# 2020.net
KiCad netlist of a schematic drawn in Altium Designer
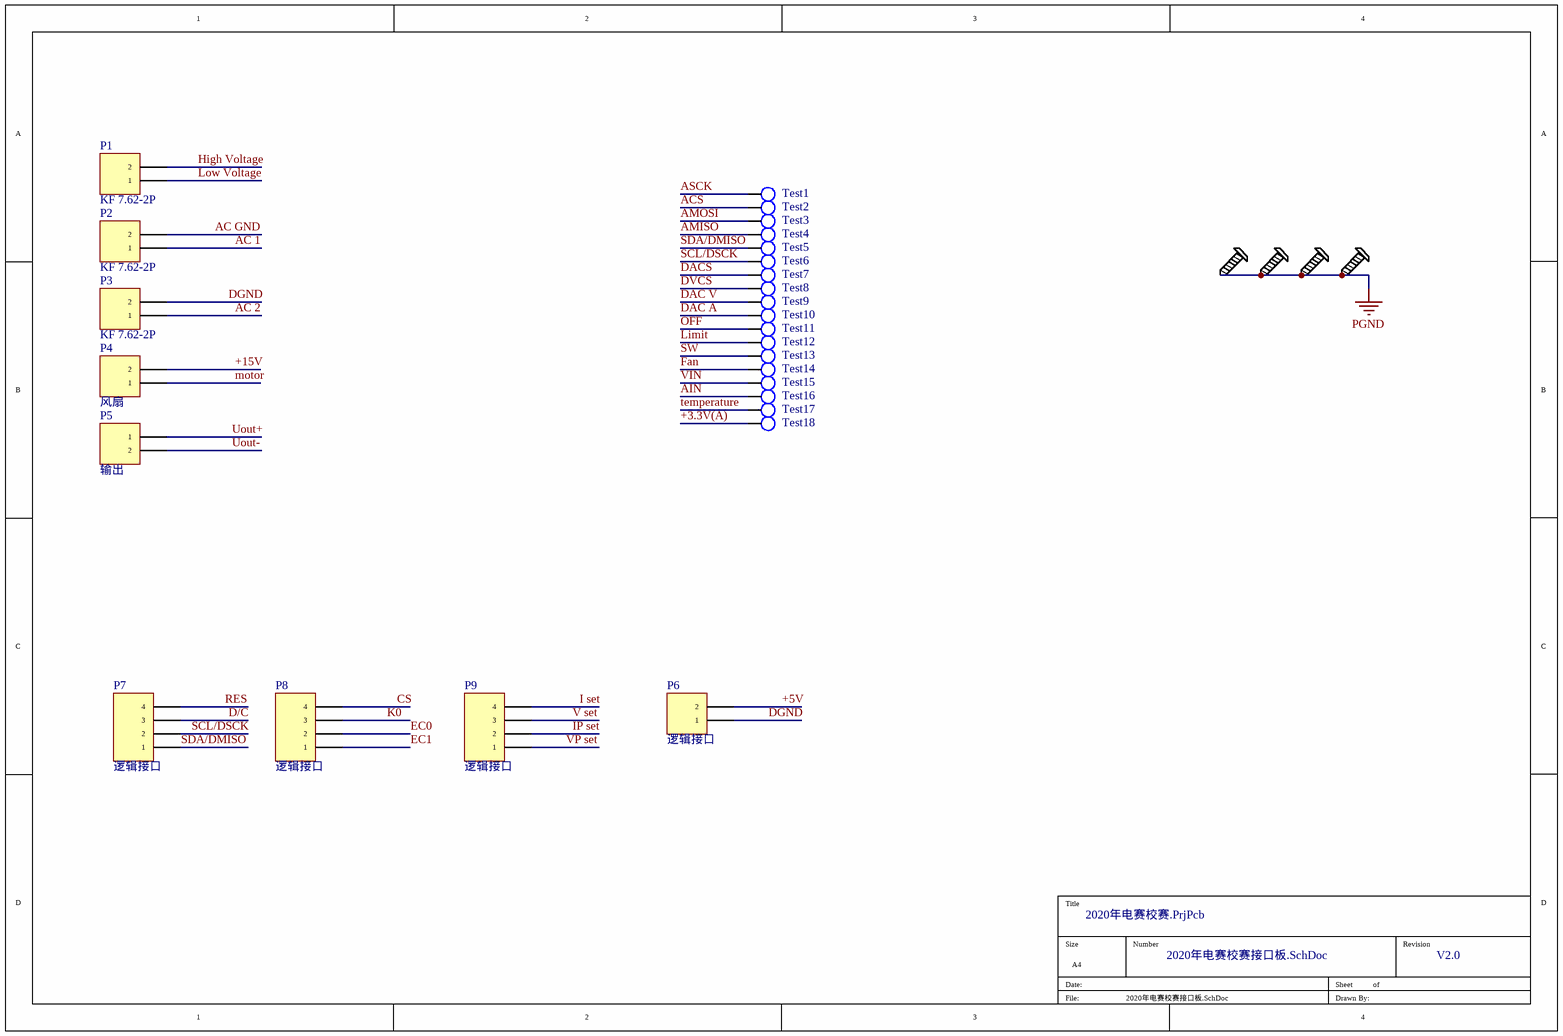
[diagram p0: 2020年电赛校赛接口板.SchDoc]

(export (version "E")
  (design (tool "Eeschema 10.0.6"))
  (components
    (comp (ref "P1")
      (value "KF 7.62-2P")
      (footprint "KF7.62-2P")
      (description "Header, 2-Pin")
      (fields (field (name "PUBLISHER") "Altium Limited"))
      (libsource (lib "Miscellaneous Connectors") (part "Header 2"))
    )
    (comp (ref "P2")
      (value "KF 7.62-2P")
      (footprint "KF7.62-2P")
      (description "Header, 2-Pin")
      (fields (field (name "PUBLISHER") "Altium Limited"))
      (libsource (lib "Miscellaneous Connectors") (part "Header 2"))
    )
    (comp (ref "P3")
      (value "KF 7.62-2P")
      (footprint "KF7.62-2P")
      (description "Header, 2-Pin")
      (fields (field (name "PUBLISHER") "Altium Limited"))
      (libsource (lib "Miscellaneous Connectors") (part "Header 2"))
    )
    (comp (ref "P4")
      (value "风扇")
      (footprint "XH2.54-2P")
      (description "Header, 2-Pin")
      (fields (field (name "PUBLISHER") "Altium Limited"))
      (libsource (lib "Miscellaneous Connectors") (part "Header 2"))
    )
    (comp (ref "P5")
      (value "输出")
      (footprint "KF7.62-2P")
      (description "Header, 2-Pin")
      (fields (field (name "PUBLISHER") "Altium Limited"))
      (libsource (lib "") (part "Header 2_1"))
    )
    (comp (ref "P6")
      (value "逻辑接口")
      (footprint "XH2.54-2P")
      (description "Header, 2-Pin")
      (fields (field (name "PUBLISHER") "Altium Limited"))
      (libsource (lib "Miscellaneous Connectors") (part "Header 2"))
    )
    (comp (ref "P7")
      (value "逻辑接口")
      (footprint "XH2.54-4P")
      (description "Header, 4-Pin")
      (fields (field (name "PUBLISHER") "Altium Limited"))
      (libsource (lib "Miscellaneous Connectors") (part "Header 4"))
    )
    (comp (ref "P8")
      (value "逻辑接口")
      (footprint "XH2.54-4P")
      (description "Header, 4-Pin")
      (fields (field (name "PUBLISHER") "Altium Limited"))
      (libsource (lib "Miscellaneous Connectors") (part "Header 4"))
    )
    (comp (ref "P9")
      (value "逻辑接口")
      (footprint "XH2.54-4P")
      (description "Header, 4-Pin")
      (fields (field (name "PUBLISHER") "Altium Limited"))
      (libsource (lib "Miscellaneous Connectors") (part "Header 4"))
    )
    (comp (ref "S2") (value "M3铜柱") (footprint "M3x4+6_L") (libsource (lib "原理图库") (part "M3铜柱")))
    (comp (ref "S3") (value "M3铜柱") (footprint "M3x4+6_L") (libsource (lib "原理图库") (part "M3铜柱")))
    (comp (ref "S4") (value "M3铜柱") (footprint "M3x4+6_L") (libsource (lib "原理图库") (part "M3铜柱")))
    (comp (ref "S5") (value "M3铜柱") (footprint "M3x4+6_L") (libsource (lib "原理图库") (part "M3铜柱")))
    (comp (ref "Test1") (value "测试点") (footprint "point") (libsource (lib "原理图库") (part "测试点")))
    (comp (ref "Test2") (value "测试点") (footprint "point") (libsource (lib "原理图库") (part "测试点")))
    (comp (ref "Test3") (value "测试点") (footprint "point") (libsource (lib "原理图库") (part "测试点")))
    (comp (ref "Test4") (value "测试点") (footprint "point") (libsource (lib "原理图库") (part "测试点")))
    (comp (ref "Test5") (value "测试点") (footprint "point") (libsource (lib "原理图库") (part "测试点")))
    (comp (ref "Test6") (value "测试点") (footprint "point") (libsource (lib "原理图库") (part "测试点")))
    (comp (ref "Test7") (value "测试点") (footprint "point") (libsource (lib "原理图库") (part "测试点")))
    (comp (ref "Test8") (value "测试点") (footprint "point") (libsource (lib "原理图库") (part "测试点")))
    (comp (ref "Test9") (value "测试点") (footprint "point") (libsource (lib "原理图库") (part "测试点")))
    (comp (ref "Test10") (value "测试点") (footprint "point") (libsource (lib "原理图库") (part "测试点")))
    (comp (ref "Test11") (value "测试点") (footprint "point") (libsource (lib "原理图库") (part "测试点")))
    (comp (ref "Test12") (value "测试点") (footprint "point") (libsource (lib "原理图库") (part "测试点")))
    (comp (ref "Test13") (value "测试点") (footprint "point") (libsource (lib "原理图库") (part "测试点")))
    (comp (ref "Test14") (value "测试点") (footprint "point") (libsource (lib "原理图库") (part "测试点")))
    (comp (ref "Test15") (value "测试点") (footprint "point") (libsource (lib "原理图库") (part "测试点")))
    (comp (ref "Test16") (value "测试点") (footprint "point") (libsource (lib "原理图库") (part "测试点")))
    (comp (ref "Test17") (value "测试点") (footprint "point") (libsource (lib "原理图库") (part "测试点")))
    (comp (ref "Test18") (value "测试点") (footprint "point") (libsource (lib "原理图库") (part "测试点")))
  )
  (nets
    (net (code "1") (name "/+3.3V(A)") (class "Default")
      (node (ref "Test18") (pin "1") (pinfunction "测试点_1") (pintype "passive"))
    )
    (net (code "2") (name "/+5V") (class "Default")
      (node (ref "P6") (pin "2") (pinfunction "2_2") (pintype "passive"))
    )
    (net (code "3") (name "/+15V") (class "Default")
      (node (ref "P4") (pin "2") (pinfunction "2_2") (pintype "passive"))
    )
    (net (code "4") (name "/AC 1") (class "Default")
      (node (ref "P2") (pin "1") (pinfunction "1_1") (pintype "passive"))
    )
    (net (code "5") (name "/AC 2") (class "Default")
      (node (ref "P3") (pin "1") (pinfunction "1_1") (pintype "passive"))
    )
    (net (code "6") (name "/AC GND") (class "Default")
      (node (ref "P2") (pin "2") (pinfunction "2_2") (pintype "passive"))
    )
    (net (code "7") (name "/ACS") (class "Default")
      (node (ref "Test2") (pin "1") (pinfunction "测试点_1") (pintype "passive"))
    )
    (net (code "8") (name "/AIN") (class "Default")
      (node (ref "Test16") (pin "1") (pinfunction "测试点_1") (pintype "passive"))
    )
    (net (code "9") (name "/AMISO") (class "Default")
      (node (ref "Test4") (pin "1") (pinfunction "测试点_1") (pintype "passive"))
    )
    (net (code "10") (name "/AMOSI") (class "Default")
      (node (ref "Test3") (pin "1") (pinfunction "测试点_1") (pintype "passive"))
    )
    (net (code "11") (name "/ASCK") (class "Default")
      (node (ref "Test1") (pin "1") (pinfunction "测试点_1") (pintype "passive"))
    )
    (net (code "12") (name "/CS") (class "Default")
      (node (ref "P8") (pin "4") (pinfunction "4_4") (pintype "passive"))
    )
    (net (code "13") (name "/DAC A") (class "Default")
      (node (ref "Test10") (pin "1") (pinfunction "测试点_1") (pintype "passive"))
    )
    (net (code "14") (name "/DAC V") (class "Default")
      (node (ref "Test9") (pin "1") (pinfunction "测试点_1") (pintype "passive"))
    )
    (net (code "15") (name "/DACS") (class "Default")
      (node (ref "Test7") (pin "1") (pinfunction "测试点_1") (pintype "passive"))
    )
    (net (code "16") (name "/DGND") (class "Default")
      (node (ref "P3") (pin "2") (pinfunction "2_2") (pintype "passive"))
      (node (ref "P6") (pin "1") (pinfunction "1_1") (pintype "passive"))
    )
    (net (code "17") (name "/DVCS") (class "Default")
      (node (ref "Test8") (pin "1") (pinfunction "测试点_1") (pintype "passive"))
    )
    (net (code "18") (name "/D{slash}C") (class "Default")
      (node (ref "P7") (pin "3") (pinfunction "3_3") (pintype "passive"))
    )
    (net (code "19") (name "/EC0") (class "Default")
      (node (ref "P8") (pin "2") (pinfunction "2_2") (pintype "passive"))
    )
    (net (code "20") (name "/EC1") (class "Default")
      (node (ref "P8") (pin "1") (pinfunction "1_1") (pintype "passive"))
    )
    (net (code "21") (name "/Fan") (class "Default")
      (node (ref "Test14") (pin "1") (pinfunction "测试点_1") (pintype "passive"))
    )
    (net (code "22") (name "/High Voltage") (class "Default")
      (node (ref "P1") (pin "2") (pinfunction "2_2") (pintype "passive"))
    )
    (net (code "23") (name "/I set") (class "Default")
      (node (ref "P9") (pin "4") (pinfunction "4_4") (pintype "passive"))
    )
    (net (code "24") (name "/IP set") (class "Default")
      (node (ref "P9") (pin "2") (pinfunction "2_2") (pintype "passive"))
    )
    (net (code "25") (name "/K0") (class "Default")
      (node (ref "P8") (pin "3") (pinfunction "3_3") (pintype "passive"))
    )
    (net (code "26") (name "/Limit") (class "Default")
      (node (ref "Test12") (pin "1") (pinfunction "测试点_1") (pintype "passive"))
    )
    (net (code "27") (name "/Low Voltage") (class "Default")
      (node (ref "P1") (pin "1") (pinfunction "1_1") (pintype "passive"))
    )
    (net (code "28") (name "/OFF") (class "Default")
      (node (ref "Test11") (pin "1") (pinfunction "测试点_1") (pintype "passive"))
    )
    (net (code "29") (name "/RES") (class "Default")
      (node (ref "P7") (pin "4") (pinfunction "4_4") (pintype "passive"))
    )
    (net (code "30") (name "/SCL{slash}DSCK") (class "Default")
      (node (ref "P7") (pin "2") (pinfunction "2_2") (pintype "passive"))
      (node (ref "Test6") (pin "1") (pinfunction "测试点_1") (pintype "passive"))
    )
    (net (code "31") (name "/SDA{slash}DMISO") (class "Default")
      (node (ref "P7") (pin "1") (pinfunction "1_1") (pintype "passive"))
      (node (ref "Test5") (pin "1") (pinfunction "测试点_1") (pintype "passive"))
    )
    (net (code "32") (name "/SW") (class "Default")
      (node (ref "Test13") (pin "1") (pinfunction "测试点_1") (pintype "passive"))
    )
    (net (code "33") (name "/Uout+") (class "Default")
      (node (ref "P5") (pin "1") (pinfunction "1_1") (pintype "passive"))
    )
    (net (code "34") (name "/Uout-") (class "Default")
      (node (ref "P5") (pin "2") (pinfunction "2_2") (pintype "passive"))
    )
    (net (code "35") (name "/V set") (class "Default")
      (node (ref "P9") (pin "3") (pinfunction "3_3") (pintype "passive"))
    )
    (net (code "36") (name "/VIN") (class "Default")
      (node (ref "Test15") (pin "1") (pinfunction "测试点_1") (pintype "passive"))
    )
    (net (code "37") (name "/VP set") (class "Default")
      (node (ref "P9") (pin "1") (pinfunction "1_1") (pintype "passive"))
    )
    (net (code "38") (name "/motor") (class "Default")
      (node (ref "P4") (pin "1") (pinfunction "1_1") (pintype "passive"))
    )
    (net (code "39") (name "/temperature") (class "Default")
      (node (ref "Test17") (pin "1") (pinfunction "测试点_1") (pintype "passive"))
    )
    (net (code "40") (name "PGND") (class "Default")
      (node (ref "S2") (pin "1") (pinfunction "GND_1") (pintype "passive"))
      (node (ref "S3") (pin "1") (pinfunction "GND_1") (pintype "passive"))
      (node (ref "S4") (pin "1") (pinfunction "GND_1") (pintype "passive"))
      (node (ref "S5") (pin "1") (pinfunction "GND_1") (pintype "passive"))
    )
  )
)
